# 0_TO_9_Counter_74LS90.net
KiCad netlist of a schematic drawn in EAGLE
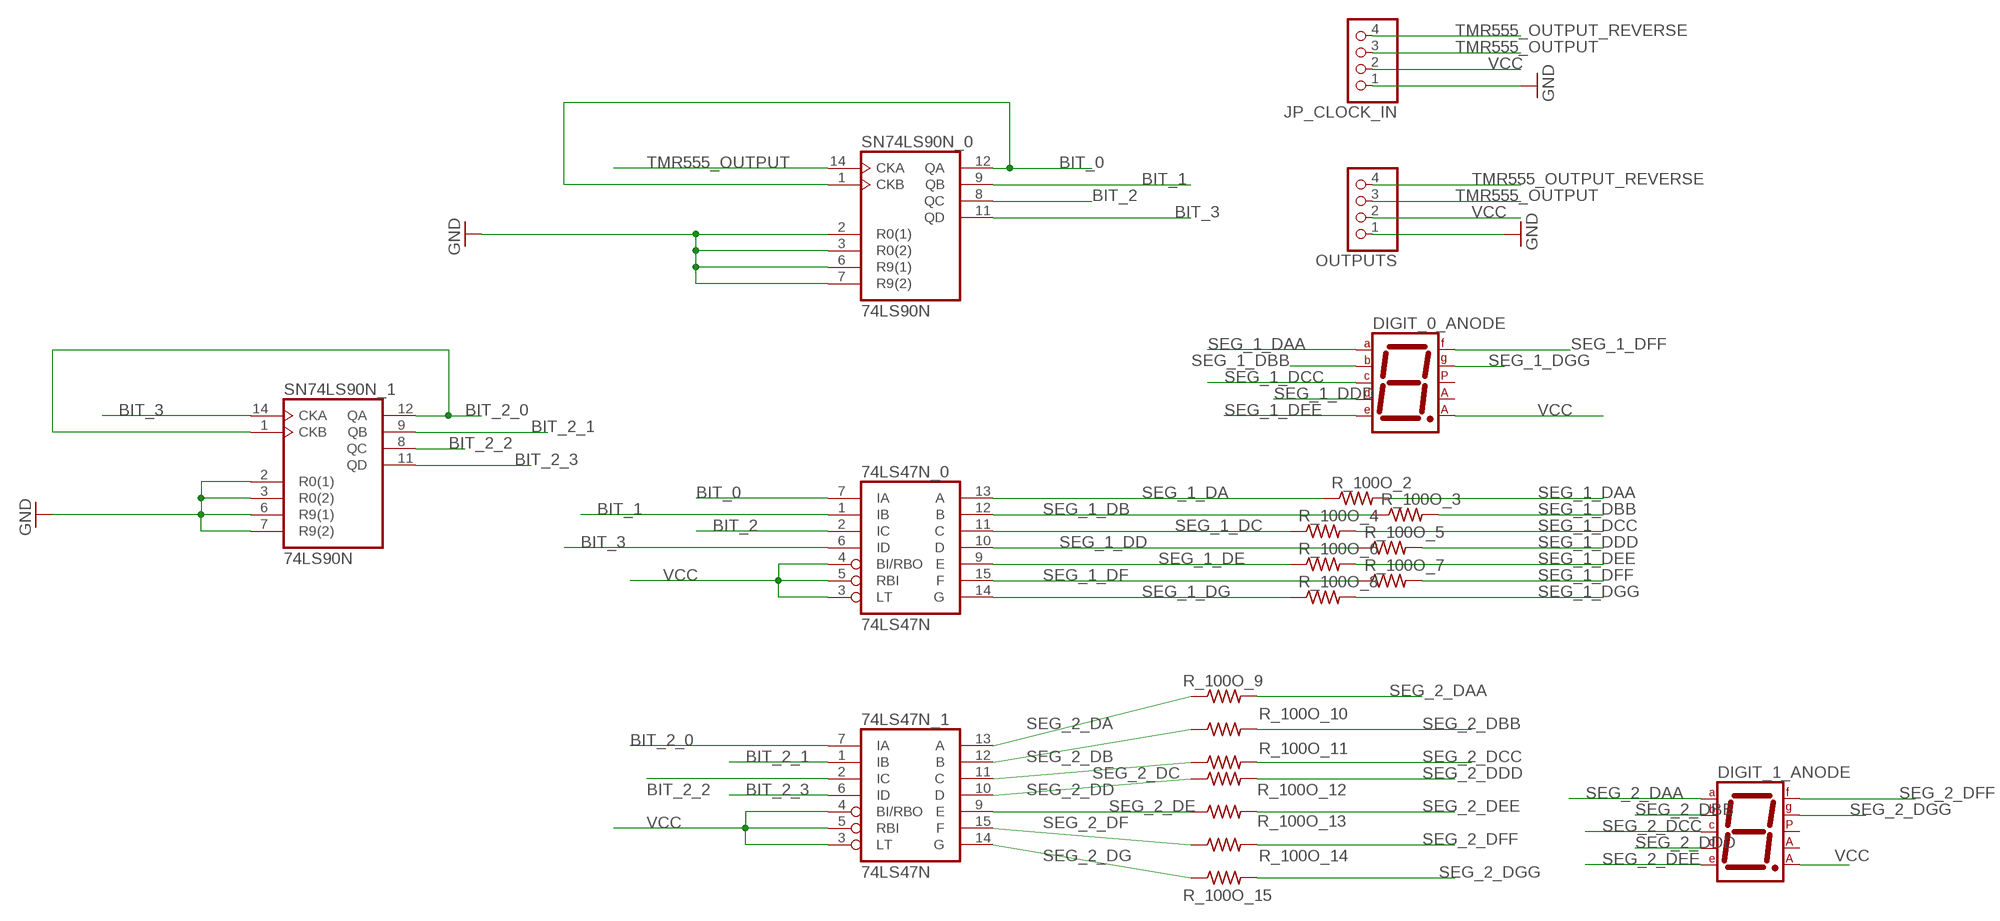
[diagram p0: schematic, sheet 1]

(export (version "E")
  (design (tool "Eeschema 10.0.6"))
  (components
    (comp (ref "74LS47N_0")
      (value "74LS47N")
      (footprint "eagle-import:DIL16")
      (libsource (lib "eagle-import") (part "7447NLS"))
    )
    (comp (ref "74LS47N_1")
      (value "74LS47N")
      (footprint "eagle-import:DIL16")
      (libsource (lib "eagle-import") (part "7447NLS"))
    )
    (comp (ref "DIGIT_0_ANODE")
      (value "7SEG-CA")
      (footprint "eagle-import:7SEG-13")
      (libsource (lib "eagle-import") (part "7SEG-CA"))
    )
    (comp (ref "DIGIT_1_ANODE")
      (value "7SEG-CA")
      (footprint "eagle-import:7SEG-13")
      (libsource (lib "eagle-import") (part "7SEG-CA"))
    )
    (comp (ref "JP_CLOCK_IN")
      (value "PINHD-1X4")
      (footprint "eagle-import:1X04")
      (libsource (lib "eagle-import") (part "PINHD-1X4"))
    )
    (comp (ref "OUTPUTS")
      (value "PINHD-1X4")
      (footprint "eagle-import:1X04")
      (libsource (lib "eagle-import") (part "PINHD-1X4"))
    )
    (comp (ref "R_100O_2")
      (value "R-US_R1206")
      (footprint "eagle-import:R1206")
      (libsource (lib "eagle-import") (part "R-US_R1206"))
    )
    (comp (ref "R_100O_3")
      (value "R-US_R1206")
      (footprint "eagle-import:R1206")
      (libsource (lib "eagle-import") (part "R-US_R1206"))
    )
    (comp (ref "R_100O_4")
      (value "R-US_R1206")
      (footprint "eagle-import:R1206")
      (libsource (lib "eagle-import") (part "R-US_R1206"))
    )
    (comp (ref "R_100O_5")
      (value "R-US_R1206")
      (footprint "eagle-import:R1206")
      (libsource (lib "eagle-import") (part "R-US_R1206"))
    )
    (comp (ref "R_100O_6")
      (value "R-US_R1206")
      (footprint "eagle-import:R1206")
      (libsource (lib "eagle-import") (part "R-US_R1206"))
    )
    (comp (ref "R_100O_7")
      (value "R-US_R1206")
      (footprint "eagle-import:R1206")
      (libsource (lib "eagle-import") (part "R-US_R1206"))
    )
    (comp (ref "R_100O_8")
      (value "R-US_R1206")
      (footprint "eagle-import:R1206")
      (libsource (lib "eagle-import") (part "R-US_R1206"))
    )
    (comp (ref "R_100O_9")
      (value "R-US_R1206")
      (footprint "eagle-import:R1206")
      (libsource (lib "eagle-import") (part "R-US_R1206"))
    )
    (comp (ref "R_100O_10")
      (value "R-US_R1206")
      (footprint "eagle-import:R1206")
      (libsource (lib "eagle-import") (part "R-US_R1206"))
    )
    (comp (ref "R_100O_11")
      (value "R-US_R1206")
      (footprint "eagle-import:R1206")
      (libsource (lib "eagle-import") (part "R-US_R1206"))
    )
    (comp (ref "R_100O_12")
      (value "R-US_R1206")
      (footprint "eagle-import:R1206")
      (libsource (lib "eagle-import") (part "R-US_R1206"))
    )
    (comp (ref "R_100O_13")
      (value "R-US_R1206")
      (footprint "eagle-import:R1206")
      (libsource (lib "eagle-import") (part "R-US_R1206"))
    )
    (comp (ref "R_100O_14")
      (value "R-US_R1206")
      (footprint "eagle-import:R1206")
      (libsource (lib "eagle-import") (part "R-US_R1206"))
    )
    (comp (ref "R_100O_15")
      (value "R-US_R1206")
      (footprint "eagle-import:R1206")
      (libsource (lib "eagle-import") (part "R-US_R1206"))
    )
    (comp (ref "SN74LS90N_0")
      (value "74LS90N")
      (footprint "eagle-import:DIL14")
      (libsource (lib "eagle-import") (part "7490NLS"))
    )
    (comp (ref "SN74LS90N_1")
      (value "74LS90N")
      (footprint "eagle-import:DIL14")
      (libsource (lib "eagle-import") (part "7490NLS"))
    )
  )
  (nets
    (net (code "1") (name "/BIT_0") (class "Default")
      (node (ref "74LS47N_0") (pin "7") (pinfunction "IA_7") (pintype "input"))
      (node (ref "SN74LS90N_0") (pin "1") (pinfunction "CKB_1") (pintype "input"))
      (node (ref "SN74LS90N_0") (pin "12") (pinfunction "QA_12") (pintype "output"))
    )
    (net (code "2") (name "/BIT_1") (class "Default")
      (node (ref "74LS47N_0") (pin "1") (pinfunction "IB_1") (pintype "input"))
      (node (ref "SN74LS90N_0") (pin "9") (pinfunction "QB_9") (pintype "output"))
    )
    (net (code "3") (name "/BIT_2") (class "Default")
      (node (ref "74LS47N_0") (pin "2") (pinfunction "IC_2") (pintype "input"))
      (node (ref "SN74LS90N_0") (pin "8") (pinfunction "QC_8") (pintype "output"))
    )
    (net (code "4") (name "/BIT_2_0") (class "Default")
      (node (ref "74LS47N_1") (pin "7") (pinfunction "IA_7") (pintype "input"))
      (node (ref "SN74LS90N_1") (pin "1") (pinfunction "CKB_1") (pintype "input"))
      (node (ref "SN74LS90N_1") (pin "12") (pinfunction "QA_12") (pintype "output"))
    )
    (net (code "5") (name "/BIT_2_1") (class "Default")
      (node (ref "74LS47N_1") (pin "1") (pinfunction "IB_1") (pintype "input"))
      (node (ref "SN74LS90N_1") (pin "9") (pinfunction "QB_9") (pintype "output"))
    )
    (net (code "6") (name "/BIT_2_2") (class "Default")
      (node (ref "74LS47N_1") (pin "2") (pinfunction "IC_2") (pintype "input"))
      (node (ref "SN74LS90N_1") (pin "8") (pinfunction "QC_8") (pintype "output"))
    )
    (net (code "7") (name "/BIT_2_3") (class "Default")
      (node (ref "74LS47N_1") (pin "6") (pinfunction "ID_6") (pintype "input"))
      (node (ref "SN74LS90N_1") (pin "11") (pinfunction "QD_11") (pintype "output"))
    )
    (net (code "8") (name "/BIT_3") (class "Default")
      (node (ref "74LS47N_0") (pin "6") (pinfunction "ID_6") (pintype "input"))
      (node (ref "SN74LS90N_0") (pin "11") (pinfunction "QD_11") (pintype "output"))
      (node (ref "SN74LS90N_1") (pin "14") (pinfunction "CKA_14") (pintype "input"))
    )
    (net (code "9") (name "/SEG_1_DA") (class "Default")
      (node (ref "74LS47N_0") (pin "13") (pinfunction "A_13") (pintype "output"))
      (node (ref "R_100O_2") (pin "1") (pinfunction "1_1") (pintype "passive"))
    )
    (net (code "10") (name "/SEG_1_DAA") (class "Default")
      (node (ref "DIGIT_0_ANODE") (pin "7") (pinfunction "A_7") (pintype "passive"))
      (node (ref "R_100O_2") (pin "2") (pinfunction "2_2") (pintype "passive"))
    )
    (net (code "11") (name "/SEG_1_DB") (class "Default")
      (node (ref "74LS47N_0") (pin "12") (pinfunction "B_12") (pintype "output"))
      (node (ref "R_100O_3") (pin "1") (pinfunction "1_1") (pintype "passive"))
    )
    (net (code "12") (name "/SEG_1_DBB") (class "Default")
      (node (ref "DIGIT_0_ANODE") (pin "6") (pinfunction "B_6") (pintype "passive"))
      (node (ref "R_100O_3") (pin "2") (pinfunction "2_2") (pintype "passive"))
    )
    (net (code "13") (name "/SEG_1_DC") (class "Default")
      (node (ref "74LS47N_0") (pin "11") (pinfunction "C_11") (pintype "output"))
      (node (ref "R_100O_4") (pin "1") (pinfunction "1_1") (pintype "passive"))
    )
    (net (code "14") (name "/SEG_1_DCC") (class "Default")
      (node (ref "DIGIT_0_ANODE") (pin "4") (pinfunction "C_4") (pintype "passive"))
      (node (ref "R_100O_4") (pin "2") (pinfunction "2_2") (pintype "passive"))
    )
    (net (code "15") (name "/SEG_1_DD") (class "Default")
      (node (ref "74LS47N_0") (pin "10") (pinfunction "D_10") (pintype "output"))
      (node (ref "R_100O_5") (pin "1") (pinfunction "1_1") (pintype "passive"))
    )
    (net (code "16") (name "/SEG_1_DDD") (class "Default")
      (node (ref "DIGIT_0_ANODE") (pin "2") (pinfunction "D_2") (pintype "passive"))
      (node (ref "R_100O_5") (pin "2") (pinfunction "2_2") (pintype "passive"))
    )
    (net (code "17") (name "/SEG_1_DE") (class "Default")
      (node (ref "74LS47N_0") (pin "9") (pinfunction "E_9") (pintype "output"))
      (node (ref "R_100O_6") (pin "1") (pinfunction "1_1") (pintype "passive"))
    )
    (net (code "18") (name "/SEG_1_DEE") (class "Default")
      (node (ref "DIGIT_0_ANODE") (pin "1") (pinfunction "E_1") (pintype "passive"))
      (node (ref "R_100O_6") (pin "2") (pinfunction "2_2") (pintype "passive"))
    )
    (net (code "19") (name "/SEG_1_DF") (class "Default")
      (node (ref "74LS47N_0") (pin "15") (pinfunction "F_15") (pintype "output"))
      (node (ref "R_100O_7") (pin "1") (pinfunction "1_1") (pintype "passive"))
    )
    (net (code "20") (name "/SEG_1_DFF") (class "Default")
      (node (ref "DIGIT_0_ANODE") (pin "9") (pinfunction "F_9") (pintype "passive"))
      (node (ref "R_100O_7") (pin "2") (pinfunction "2_2") (pintype "passive"))
    )
    (net (code "21") (name "/SEG_1_DG") (class "Default")
      (node (ref "74LS47N_0") (pin "14") (pinfunction "G_14") (pintype "output"))
      (node (ref "R_100O_8") (pin "1") (pinfunction "1_1") (pintype "passive"))
    )
    (net (code "22") (name "/SEG_1_DGG") (class "Default")
      (node (ref "DIGIT_0_ANODE") (pin "10") (pinfunction "G_10") (pintype "passive"))
      (node (ref "R_100O_8") (pin "2") (pinfunction "2_2") (pintype "passive"))
    )
    (net (code "23") (name "/SEG_2_DA") (class "Default")
      (node (ref "74LS47N_1") (pin "13") (pinfunction "A_13") (pintype "output"))
      (node (ref "R_100O_9") (pin "1") (pinfunction "1_1") (pintype "passive"))
    )
    (net (code "24") (name "/SEG_2_DAA") (class "Default")
      (node (ref "DIGIT_1_ANODE") (pin "7") (pinfunction "A_7") (pintype "passive"))
      (node (ref "R_100O_9") (pin "2") (pinfunction "2_2") (pintype "passive"))
    )
    (net (code "25") (name "/SEG_2_DB") (class "Default")
      (node (ref "74LS47N_1") (pin "12") (pinfunction "B_12") (pintype "output"))
      (node (ref "R_100O_10") (pin "1") (pinfunction "1_1") (pintype "passive"))
    )
    (net (code "26") (name "/SEG_2_DBB") (class "Default")
      (node (ref "DIGIT_1_ANODE") (pin "6") (pinfunction "B_6") (pintype "passive"))
      (node (ref "R_100O_10") (pin "2") (pinfunction "2_2") (pintype "passive"))
    )
    (net (code "27") (name "/SEG_2_DC") (class "Default")
      (node (ref "74LS47N_1") (pin "11") (pinfunction "C_11") (pintype "output"))
      (node (ref "R_100O_11") (pin "1") (pinfunction "1_1") (pintype "passive"))
    )
    (net (code "28") (name "/SEG_2_DCC") (class "Default")
      (node (ref "DIGIT_1_ANODE") (pin "4") (pinfunction "C_4") (pintype "passive"))
      (node (ref "R_100O_11") (pin "2") (pinfunction "2_2") (pintype "passive"))
    )
    (net (code "29") (name "/SEG_2_DD") (class "Default")
      (node (ref "74LS47N_1") (pin "10") (pinfunction "D_10") (pintype "output"))
      (node (ref "R_100O_12") (pin "1") (pinfunction "1_1") (pintype "passive"))
    )
    (net (code "30") (name "/SEG_2_DDD") (class "Default")
      (node (ref "DIGIT_1_ANODE") (pin "2") (pinfunction "D_2") (pintype "passive"))
      (node (ref "R_100O_12") (pin "2") (pinfunction "2_2") (pintype "passive"))
    )
    (net (code "31") (name "/SEG_2_DE") (class "Default")
      (node (ref "74LS47N_1") (pin "9") (pinfunction "E_9") (pintype "output"))
      (node (ref "R_100O_13") (pin "1") (pinfunction "1_1") (pintype "passive"))
    )
    (net (code "32") (name "/SEG_2_DEE") (class "Default")
      (node (ref "DIGIT_1_ANODE") (pin "1") (pinfunction "E_1") (pintype "passive"))
      (node (ref "R_100O_13") (pin "2") (pinfunction "2_2") (pintype "passive"))
    )
    (net (code "33") (name "/SEG_2_DF") (class "Default")
      (node (ref "74LS47N_1") (pin "15") (pinfunction "F_15") (pintype "output"))
      (node (ref "R_100O_14") (pin "1") (pinfunction "1_1") (pintype "passive"))
    )
    (net (code "34") (name "/SEG_2_DFF") (class "Default")
      (node (ref "DIGIT_1_ANODE") (pin "9") (pinfunction "F_9") (pintype "passive"))
      (node (ref "R_100O_14") (pin "2") (pinfunction "2_2") (pintype "passive"))
    )
    (net (code "35") (name "/SEG_2_DG") (class "Default")
      (node (ref "74LS47N_1") (pin "14") (pinfunction "G_14") (pintype "output"))
      (node (ref "R_100O_15") (pin "1") (pinfunction "1_1") (pintype "passive"))
    )
    (net (code "36") (name "/SEG_2_DGG") (class "Default")
      (node (ref "DIGIT_1_ANODE") (pin "10") (pinfunction "G_10") (pintype "passive"))
      (node (ref "R_100O_15") (pin "2") (pinfunction "2_2") (pintype "passive"))
    )
    (net (code "37") (name "/TMR555_OUTPUT") (class "Default")
      (node (ref "JP_CLOCK_IN") (pin "3") (pinfunction "3_3") (pintype "passive"))
      (node (ref "OUTPUTS") (pin "3") (pinfunction "3_3") (pintype "passive"))
      (node (ref "SN74LS90N_0") (pin "14") (pinfunction "CKA_14") (pintype "input"))
    )
    (net (code "38") (name "/TMR555_OUTPUT_REVERSE") (class "Default")
      (node (ref "JP_CLOCK_IN") (pin "4") (pinfunction "4_4") (pintype "passive"))
      (node (ref "OUTPUTS") (pin "4") (pinfunction "4_4") (pintype "passive"))
    )
    (net (code "39") (name "/VCC") (class "Default")
      (node (ref "74LS47N_0") (pin "3") (pinfunction "LT_3") (pintype "input"))
      (node (ref "74LS47N_0") (pin "4") (pinfunction "BI/RBO_4") (pintype "input"))
      (node (ref "74LS47N_0") (pin "5") (pinfunction "RBI_5") (pintype "input"))
      (node (ref "74LS47N_1") (pin "3") (pinfunction "LT_3") (pintype "input"))
      (node (ref "74LS47N_1") (pin "4") (pinfunction "BI/RBO_4") (pintype "input"))
      (node (ref "74LS47N_1") (pin "5") (pinfunction "RBI_5") (pintype "input"))
      (node (ref "DIGIT_0_ANODE") (pin "8") (pinfunction "CA2_8") (pintype "passive"))
      (node (ref "DIGIT_1_ANODE") (pin "8") (pinfunction "CA2_8") (pintype "passive"))
      (node (ref "JP_CLOCK_IN") (pin "2") (pinfunction "2_2") (pintype "passive"))
      (node (ref "OUTPUTS") (pin "2") (pinfunction "2_2") (pintype "passive"))
    )
    (net (code "40") (name "GND") (class "Default")
      (node (ref "JP_CLOCK_IN") (pin "1") (pinfunction "1_1") (pintype "passive"))
      (node (ref "OUTPUTS") (pin "1") (pinfunction "1_1") (pintype "passive"))
      (node (ref "SN74LS90N_0") (pin "2") (pinfunction "R0(1)_2") (pintype "input"))
      (node (ref "SN74LS90N_0") (pin "3") (pinfunction "R0(2)_3") (pintype "input"))
      (node (ref "SN74LS90N_0") (pin "6") (pinfunction "R9(1)_6") (pintype "input"))
      (node (ref "SN74LS90N_0") (pin "7") (pinfunction "R9(2)_7") (pintype "input"))
      (node (ref "SN74LS90N_1") (pin "2") (pinfunction "R0(1)_2") (pintype "input"))
      (node (ref "SN74LS90N_1") (pin "3") (pinfunction "R0(2)_3") (pintype "input"))
      (node (ref "SN74LS90N_1") (pin "6") (pinfunction "R9(1)_6") (pintype "input"))
      (node (ref "SN74LS90N_1") (pin "7") (pinfunction "R9(2)_7") (pintype "input"))
    )
    (net (code "41") (name "unconnected-(DIGIT_0_ANODE-CA1-Pad3)") (class "Default")
      (node (ref "DIGIT_0_ANODE") (pin "3") (pinfunction "CA1_3") (pintype "passive"))
    )
    (net (code "42") (name "unconnected-(DIGIT_0_ANODE-DP-Pad5)") (class "Default")
      (node (ref "DIGIT_0_ANODE") (pin "5") (pinfunction "DP_5") (pintype "passive"))
    )
    (net (code "43") (name "unconnected-(DIGIT_1_ANODE-CA1-Pad3)") (class "Default")
      (node (ref "DIGIT_1_ANODE") (pin "3") (pinfunction "CA1_3") (pintype "passive"))
    )
    (net (code "44") (name "unconnected-(DIGIT_1_ANODE-DP-Pad5)") (class "Default")
      (node (ref "DIGIT_1_ANODE") (pin "5") (pinfunction "DP_5") (pintype "passive"))
    )
  )
)
